# demo1.net
KiCad netlist of a schematic drawn in Altium Designer
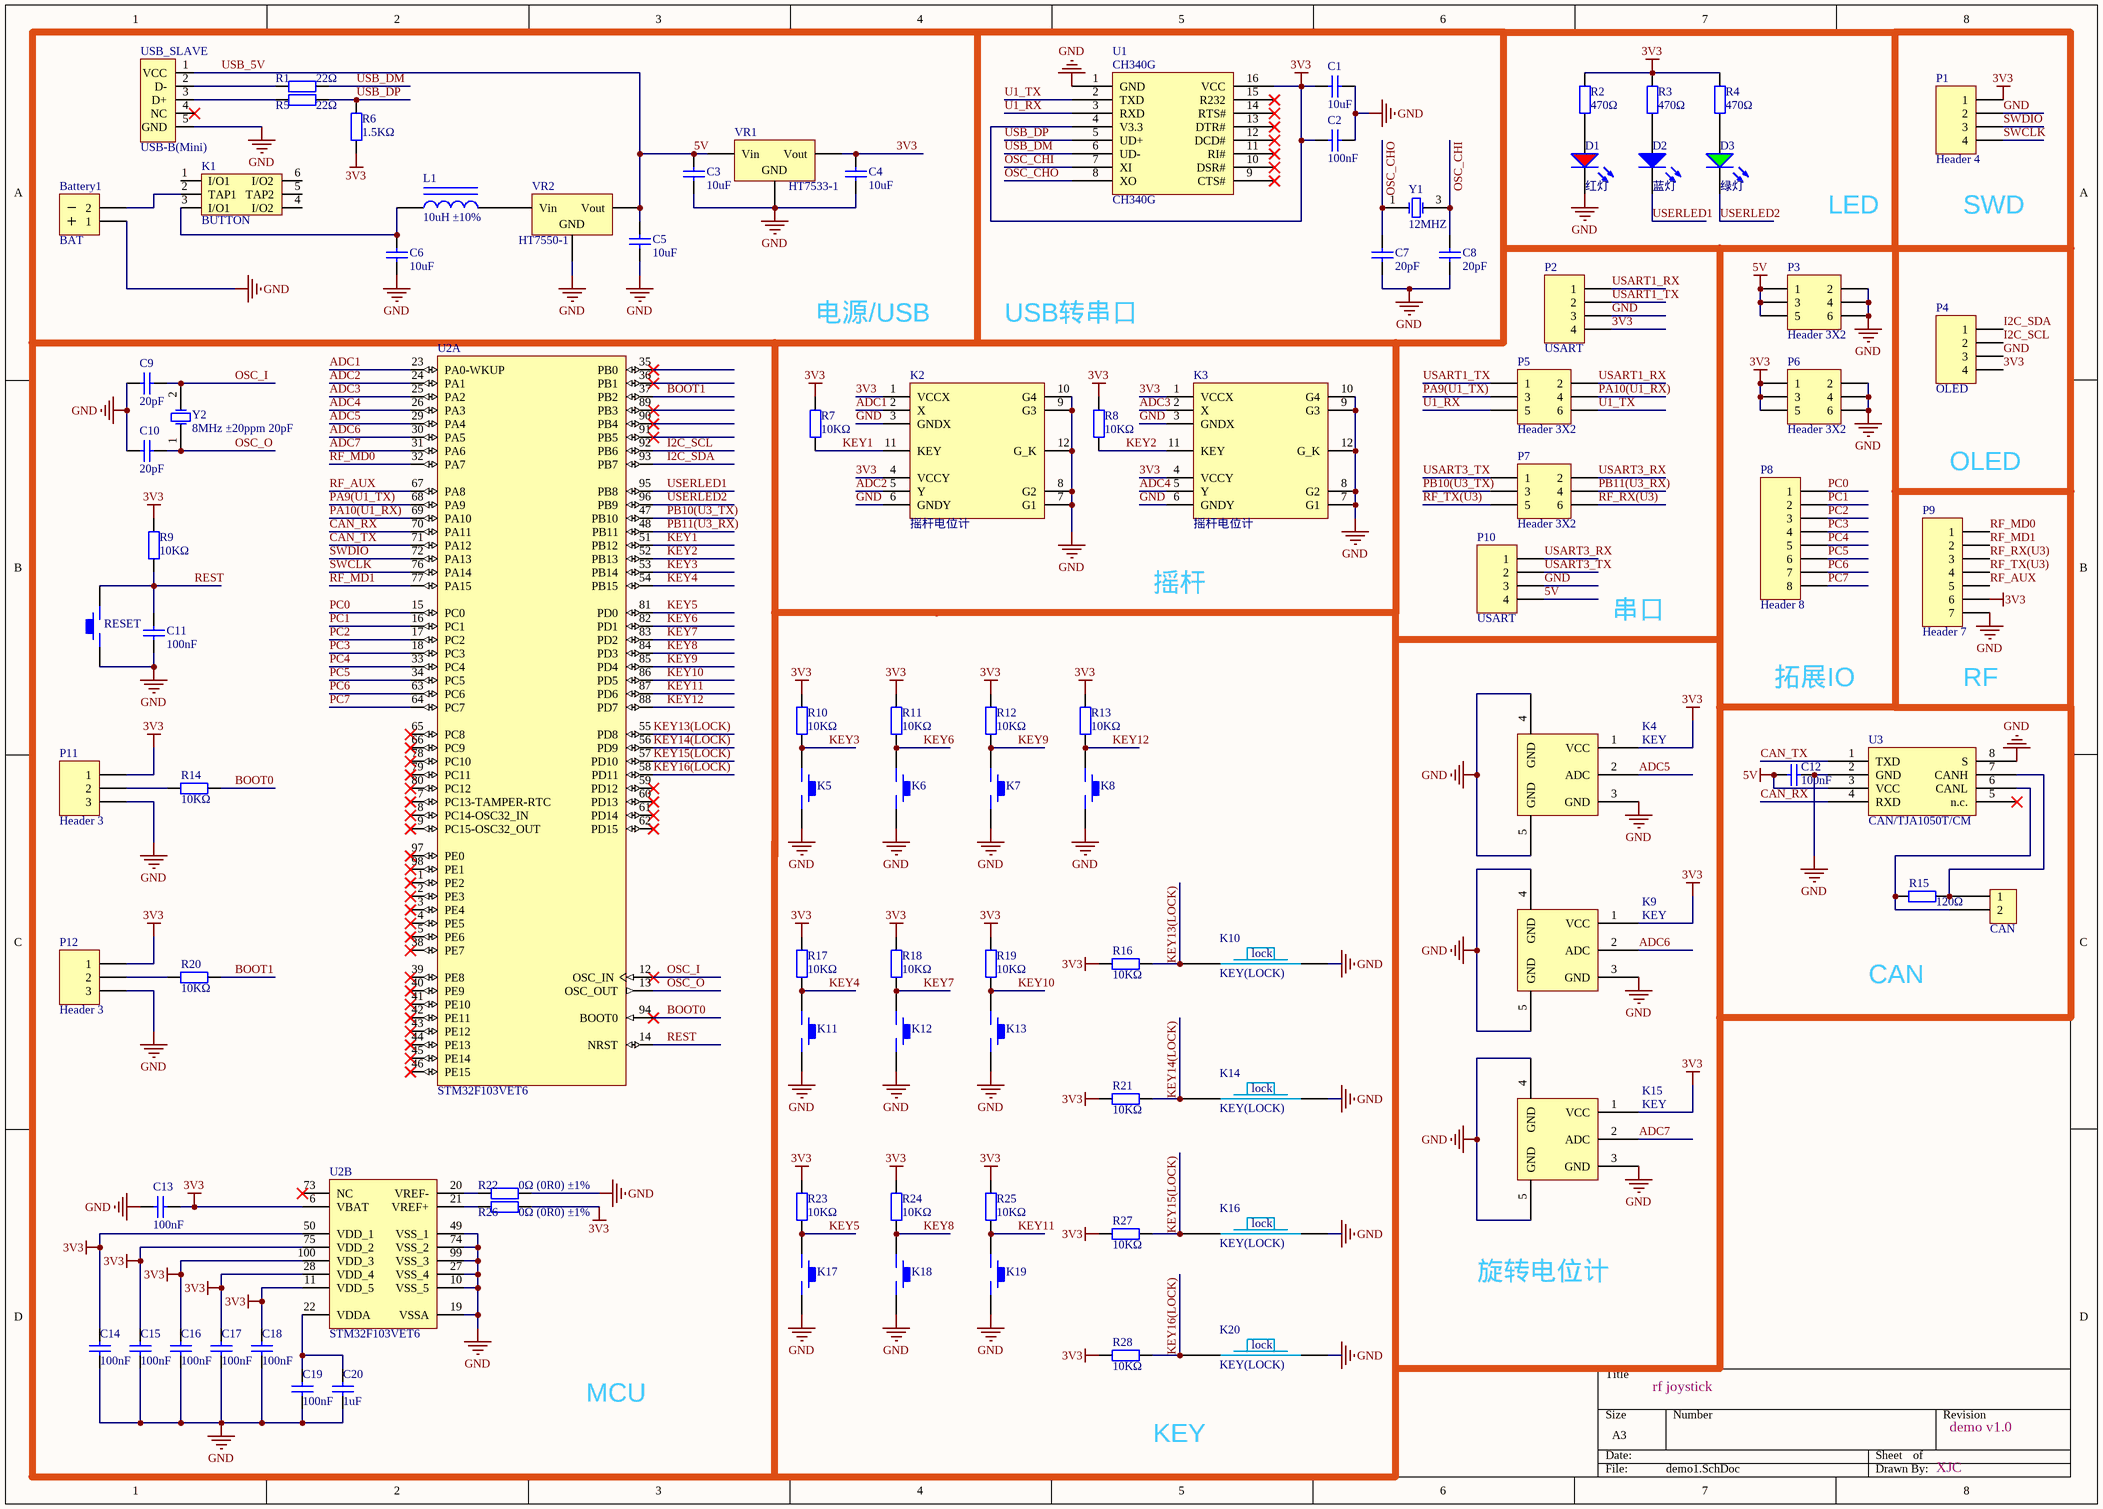
[diagram p0: demo1.SchDoc]

(export (version "E")
  (design (tool "Eeschema 10.0.6"))
  (components
    (comp (ref "*1") (value "CAN") (footprint "CAN") (libsource (lib "摇杆电位计") (part "CAN")))
    (comp (ref "Battery1")
      (value "BAT")
      (footprint "HDR1X2")
      (description "Header, 2-Pin")
      (fields (field (name "PUBLISHER") "mazhongwei"))
      (libsource (lib "RoboFly") (part "BAT"))
    )
    (comp (ref "C1")
      (value "10uF")
      (footprint "0603_C")
      (description "贴片电容")
      (libsource (lib "Cap") (part "0603 10uF (106) 10% 10V"))
    )
    (comp (ref "C2")
      (value "100nF")
      (footprint "0603_C")
      (description "贴片电容")
      (libsource (lib "Cap") (part "0603 100nF (104) 10% 50V"))
    )
    (comp (ref "C3")
      (value "10uF")
      (footprint "0603_C")
      (description "贴片电容")
      (libsource (lib "Cap") (part "0603 10uF (106) 10% 10V"))
    )
    (comp (ref "C4")
      (value "10uF")
      (footprint "0603_C")
      (description "贴片电容")
      (libsource (lib "Cap") (part "0603 10uF (106) 10% 10V"))
    )
    (comp (ref "C5")
      (value "10uF")
      (footprint "0603_C")
      (description "贴片电容")
      (libsource (lib "Cap") (part "0603 10uF (106) 10% 10V"))
    )
    (comp (ref "C6")
      (value "10uF")
      (footprint "0603_C")
      (description "贴片电容")
      (libsource (lib "Cap") (part "0603 10uF (106) 10% 10V"))
    )
    (comp (ref "C7")
      (value "20pF")
      (footprint "0603_C")
      (description "贴片电容")
      (libsource (lib "Cap") (part "0603 20pF (200) 5% 50V"))
    )
    (comp (ref "C8")
      (value "20pF")
      (footprint "0603_C")
      (description "贴片电容")
      (libsource (lib "Cap") (part "0603 20pF (200) 5% 50V"))
    )
    (comp (ref "C9")
      (value "20pF")
      (footprint "0603_C")
      (description "贴片电容")
      (libsource (lib "Cap") (part "0603 20pF (200) 5% 50V"))
    )
    (comp (ref "C10")
      (value "20pF")
      (footprint "0603_C")
      (description "贴片电容")
      (libsource (lib "Cap") (part "0603 20pF (200) 5% 50V"))
    )
    (comp (ref "C11")
      (value "100nF")
      (footprint "0603_C")
      (description "贴片电容")
      (libsource (lib "Cap") (part "0603 100nF (104) 10% 50V"))
    )
    (comp (ref "C12")
      (value "100nF")
      (footprint "0603_C")
      (description "贴片电容")
      (libsource (lib "Cap") (part "0603 100nF (104) 10% 50V"))
    )
    (comp (ref "C13")
      (value "100nF")
      (footprint "0603_C")
      (description "贴片电容")
      (libsource (lib "Cap") (part "0603 100nF (104) 10% 50V"))
    )
    (comp (ref "C14")
      (value "100nF")
      (footprint "0603_C")
      (description "贴片电容")
      (libsource (lib "Cap") (part "0603 100nF (104) 10% 50V"))
    )
    (comp (ref "C15")
      (value "100nF")
      (footprint "0603_C")
      (description "贴片电容")
      (libsource (lib "Cap") (part "0603 100nF (104) 10% 50V"))
    )
    (comp (ref "C16")
      (value "100nF")
      (footprint "0603_C")
      (description "贴片电容")
      (libsource (lib "Cap") (part "0603 100nF (104) 10% 50V"))
    )
    (comp (ref "C17")
      (value "100nF")
      (footprint "0603_C")
      (description "贴片电容")
      (libsource (lib "Cap") (part "0603 100nF (104) 10% 50V"))
    )
    (comp (ref "C18")
      (value "100nF")
      (footprint "0603_C")
      (description "贴片电容")
      (libsource (lib "Cap") (part "0603 100nF (104) 10% 50V"))
    )
    (comp (ref "C19")
      (value "100nF")
      (footprint "0603_C")
      (description "贴片电容")
      (libsource (lib "Cap") (part "0603 100nF (104) 10% 50V"))
    )
    (comp (ref "C20")
      (value "1uF")
      (footprint "0603_C")
      (description "贴片电容")
      (libsource (lib "Cap") (part "0603 1uF (105) 10% 50V"))
    )
    (comp (ref "D1")
      (value "红灯")
      (footprint "0603_LED_S1")
      (description "发光二极管")
      (libsource (lib "LED") (part "0603 红灯"))
    )
    (comp (ref "D2")
      (value "蓝灯")
      (footprint "0603_LED_S1")
      (description "发光二极管")
      (libsource (lib "LED") (part "0603 蓝灯"))
    )
    (comp (ref "D3")
      (value "绿灯")
      (footprint "0603_LED_S1")
      (description "发光二极管")
      (libsource (lib "LED") (part "0603 绿灯"))
    )
    (comp (ref "K1")
      (value "BUTTON")
      (footprint "BTN8.5*8.5")
      (libsource (lib "Explorer STM32F407封装库") (part "BUTTON"))
    )
    (comp (ref "K2") (value "摇杆电位计") (footprint "摇杆电位计") (libsource (lib "摇杆电位计") (part "摇杆电位计")))
    (comp (ref "K3") (value "摇杆电位计") (footprint "摇杆电位计") (libsource (lib "摇杆电位计") (part "摇杆电位计")))
    (comp (ref "K4") (value "KEY") (footprint "旋转电位计") (libsource (lib "摇杆电位计") (part "旋转电位计")))
    (comp (ref "K5")
      (value "KEY_M")
      (footprint "KEY_M")
      (libsource (lib "Explorer STM32F407封装库") (part "KEY_M"))
    )
    (comp (ref "K6")
      (value "KEY_M")
      (footprint "KEY_M")
      (libsource (lib "Explorer STM32F407封装库") (part "KEY_M"))
    )
    (comp (ref "K7")
      (value "KEY_M")
      (footprint "KEY_M")
      (libsource (lib "Explorer STM32F407封装库") (part "KEY_M"))
    )
    (comp (ref "K8")
      (value "KEY_M")
      (footprint "KEY_M")
      (libsource (lib "Explorer STM32F407封装库") (part "KEY_M"))
    )
    (comp (ref "K9") (value "KEY") (footprint "旋转电位计") (libsource (lib "摇杆电位计") (part "旋转电位计")))
    (comp (ref "K10") (value "KEY(LOCK)") (footprint "自锁按键") (libsource (lib "摇杆电位计") (part "自锁按键")))
    (comp (ref "K11")
      (value "KEY_M")
      (footprint "KEY_M")
      (libsource (lib "Explorer STM32F407封装库") (part "KEY_M"))
    )
    (comp (ref "K12")
      (value "KEY_M")
      (footprint "KEY_M")
      (libsource (lib "Explorer STM32F407封装库") (part "KEY_M"))
    )
    (comp (ref "K13")
      (value "KEY_M")
      (footprint "KEY_M")
      (libsource (lib "Explorer STM32F407封装库") (part "KEY_M"))
    )
    (comp (ref "K14") (value "KEY(LOCK)") (footprint "自锁按键") (libsource (lib "摇杆电位计") (part "自锁按键")))
    (comp (ref "K15") (value "KEY") (footprint "旋转电位计") (libsource (lib "摇杆电位计") (part "旋转电位计")))
    (comp (ref "K16") (value "KEY(LOCK)") (footprint "自锁按键") (libsource (lib "摇杆电位计") (part "自锁按键")))
    (comp (ref "K17")
      (value "KEY_M")
      (footprint "KEY_M")
      (libsource (lib "Explorer STM32F407封装库") (part "KEY_M"))
    )
    (comp (ref "K18")
      (value "KEY_M")
      (footprint "KEY_M")
      (libsource (lib "Explorer STM32F407封装库") (part "KEY_M"))
    )
    (comp (ref "K19")
      (value "KEY_M")
      (footprint "KEY_M")
      (libsource (lib "Explorer STM32F407封装库") (part "KEY_M"))
    )
    (comp (ref "K20") (value "KEY(LOCK)") (footprint "自锁按键") (libsource (lib "摇杆电位计") (part "自锁按键")))
    (comp (ref "L1")
      (value "10uH ±10%")
      (footprint "0603_L")
      (description "贴片电感")
      (libsource (lib "IUD") (part "0603 10uH 10%"))
    )
    (comp (ref "P1")
      (value "Header 4")
      (footprint "HDR1X4")
      (description "Header, 4-Pin")
      (fields (field (name "PUBLISHER") "Altium Limited"))
      (libsource (lib "Miscellaneous Connectors") (part "Header 4"))
    )
    (comp (ref "P2")
      (value "USART")
      (footprint "HDR1X4")
      (description "Header, 4-Pin")
      (fields (field (name "PUBLISHER") "Altium Limited"))
      (libsource (lib "Miscellaneous Connectors") (part "Header 4"))
    )
    (comp (ref "P3")
      (value "Header 3X2")
      (footprint "HDR2X3")
      (description "Header, 3-Pin, Dual row")
      (fields (field (name "PUBLISHER") "Altium Limited"))
      (libsource (lib "Miscellaneous Connectors") (part "Header 3X2"))
    )
    (comp (ref "P4")
      (value "OLED")
      (footprint "HDR1X4")
      (description "Header, 4-Pin")
      (fields (field (name "PUBLISHER") "Altium Limited"))
      (libsource (lib "Miscellaneous Connectors") (part "Header 4"))
    )
    (comp (ref "P5")
      (value "Header 3X2")
      (footprint "HDR2X3")
      (description "Header, 3-Pin, Dual row")
      (fields (field (name "PUBLISHER") "Altium Limited"))
      (libsource (lib "Miscellaneous Connectors") (part "Header 3X2"))
    )
    (comp (ref "P6")
      (value "Header 3X2")
      (footprint "HDR2X3")
      (description "Header, 3-Pin, Dual row")
      (fields (field (name "PUBLISHER") "Altium Limited"))
      (libsource (lib "Miscellaneous Connectors") (part "Header 3X2"))
    )
    (comp (ref "P7")
      (value "Header 3X2")
      (footprint "HDR2X3")
      (description "Header, 3-Pin, Dual row")
      (fields (field (name "PUBLISHER") "Altium Limited"))
      (libsource (lib "Miscellaneous Connectors") (part "Header 3X2"))
    )
    (comp (ref "P8")
      (value "Header 8")
      (footprint "HDR1X8")
      (description "Header, 8-Pin")
      (fields (field (name "PUBLISHER") "Altium Limited"))
      (libsource (lib "Miscellaneous Connectors") (part "Header 8"))
    )
    (comp (ref "P9")
      (value "Header 7")
      (footprint "HDR1X7")
      (description "Header, 7-Pin")
      (fields (field (name "PUBLISHER") "Altium Limited"))
      (libsource (lib "Miscellaneous Connectors") (part "Header 7"))
    )
    (comp (ref "P10")
      (value "USART")
      (footprint "HDR1X4")
      (description "Header, 4-Pin")
      (fields (field (name "PUBLISHER") "Altium Limited"))
      (libsource (lib "Miscellaneous Connectors") (part "Header 4"))
    )
    (comp (ref "P11")
      (value "Header 3")
      (footprint "HDR1X3")
      (description "Header, 3-Pin")
      (fields (field (name "PUBLISHER") "Altium Limited"))
      (libsource (lib "Miscellaneous Connectors") (part "Header 3"))
    )
    (comp (ref "P12")
      (value "Header 3")
      (footprint "HDR1X3")
      (description "Header, 3-Pin")
      (fields (field (name "PUBLISHER") "Altium Limited"))
      (libsource (lib "Miscellaneous Connectors") (part "Header 3"))
    )
    (comp (ref "R1")
      (value "22Ω")
      (footprint "0603_R")
      (description "贴片电阻")
      (libsource (lib "RES") (part "0603 22Ω (22R0) 1%"))
    )
    (comp (ref "R2")
      (value "470Ω")
      (footprint "0603_R")
      (description "贴片电阻")
      (libsource (lib "RES") (part "0603 470Ω (4700) 1%"))
    )
    (comp (ref "R3")
      (value "470Ω")
      (footprint "0603_R")
      (description "贴片电阻")
      (libsource (lib "RES") (part "0603 470Ω (4700) 1%"))
    )
    (comp (ref "R4")
      (value "470Ω")
      (footprint "0603_R")
      (description "贴片电阻")
      (libsource (lib "RES") (part "0603 470Ω (4700) 1%"))
    )
    (comp (ref "R5")
      (value "22Ω")
      (footprint "0603_R")
      (description "贴片电阻")
      (libsource (lib "RES") (part "0603 22Ω (22R0) 1%"))
    )
    (comp (ref "R6")
      (value "1.5KΩ")
      (footprint "0603_R")
      (description "贴片电阻")
      (libsource (lib "RES") (part "0603 1.5KΩ (1501) 1%"))
    )
    (comp (ref "R7")
      (value "10KΩ")
      (footprint "0603_R")
      (description "贴片电阻")
      (libsource (lib "RES") (part "0603 10KΩ (1002) 1%"))
    )
    (comp (ref "R8")
      (value "10KΩ")
      (footprint "0603_R")
      (description "贴片电阻")
      (libsource (lib "RES") (part "0603 10KΩ (1002) 1%"))
    )
    (comp (ref "R9")
      (value "10KΩ")
      (footprint "0603_R")
      (description "贴片电阻")
      (libsource (lib "RES") (part "0603 10KΩ (1002) 1%"))
    )
    (comp (ref "R10")
      (value "10KΩ")
      (footprint "0603_R")
      (description "贴片电阻")
      (libsource (lib "RES") (part "0603 10KΩ (1002) 1%"))
    )
    (comp (ref "R11")
      (value "10KΩ")
      (footprint "0603_R")
      (description "贴片电阻")
      (libsource (lib "RES") (part "0603 10KΩ (1002) 1%"))
    )
    (comp (ref "R12")
      (value "10KΩ")
      (footprint "0603_R")
      (description "贴片电阻")
      (libsource (lib "RES") (part "0603 10KΩ (1002) 1%"))
    )
    (comp (ref "R13")
      (value "10KΩ")
      (footprint "0603_R")
      (description "贴片电阻")
      (libsource (lib "RES") (part "0603 10KΩ (1002) 1%"))
    )
    (comp (ref "R14")
      (value "10KΩ")
      (footprint "0603_R")
      (description "贴片电阻")
      (libsource (lib "") (part "0603 10KΩ (1002) 1%_1"))
    )
    (comp (ref "R15")
      (value "120Ω")
      (footprint "0603_R")
      (description "贴片电阻")
      (libsource (lib "RES") (part "0603 120Ω (1200) 1%"))
    )
    (comp (ref "R16")
      (value "10KΩ")
      (footprint "0603_R")
      (description "贴片电阻")
      (libsource (lib "") (part "0603 10KΩ (1002) 1%_1"))
    )
    (comp (ref "R17")
      (value "10KΩ")
      (footprint "0603_R")
      (description "贴片电阻")
      (libsource (lib "RES") (part "0603 10KΩ (1002) 1%"))
    )
    (comp (ref "R18")
      (value "10KΩ")
      (footprint "0603_R")
      (description "贴片电阻")
      (libsource (lib "RES") (part "0603 10KΩ (1002) 1%"))
    )
    (comp (ref "R19")
      (value "10KΩ")
      (footprint "0603_R")
      (description "贴片电阻")
      (libsource (lib "RES") (part "0603 10KΩ (1002) 1%"))
    )
    (comp (ref "R20")
      (value "10KΩ")
      (footprint "0603_R")
      (description "贴片电阻")
      (libsource (lib "") (part "0603 10KΩ (1002) 1%_1"))
    )
    (comp (ref "R21")
      (value "10KΩ")
      (footprint "0603_R")
      (description "贴片电阻")
      (libsource (lib "") (part "0603 10KΩ (1002) 1%_1"))
    )
    (comp (ref "R22")
      (value "0Ω (0R0) ±1%")
      (footprint "0603_R")
      (description "贴片电阻")
      (libsource (lib "RES") (part "0603 0Ω (0R0) 1%"))
    )
    (comp (ref "R23")
      (value "10KΩ")
      (footprint "0603_R")
      (description "贴片电阻")
      (libsource (lib "RES") (part "0603 10KΩ (1002) 1%"))
    )
    (comp (ref "R24")
      (value "10KΩ")
      (footprint "0603_R")
      (description "贴片电阻")
      (libsource (lib "RES") (part "0603 10KΩ (1002) 1%"))
    )
    (comp (ref "R25")
      (value "10KΩ")
      (footprint "0603_R")
      (description "贴片电阻")
      (libsource (lib "RES") (part "0603 10KΩ (1002) 1%"))
    )
    (comp (ref "R26")
      (value "0Ω (0R0) ±1%")
      (footprint "0603_R")
      (description "贴片电阻")
      (libsource (lib "RES") (part "0603 0Ω (0R0) 1%"))
    )
    (comp (ref "R27")
      (value "10KΩ")
      (footprint "0603_R")
      (description "贴片电阻")
      (libsource (lib "") (part "0603 10KΩ (1002) 1%_1"))
    )
    (comp (ref "R28")
      (value "10KΩ")
      (footprint "0603_R")
      (description "贴片电阻")
      (libsource (lib "") (part "0603 10KΩ (1002) 1%_1"))
    )
    (comp (ref "RESET") (value "KEY_M") (footprint "KEY_M") (libsource (lib "") (part "KEY_M_1")))
    (comp (ref "U1")
      (value "CH340G")
      (footprint "SOIC-16_150mil")
      (description "USB")
      (libsource (lib "IC") (part "CH340G_[C14267]"))
    )
    (comp (ref "U2")
      (value "STM32F103VET6")
      (footprint "LQFP-100_14x14x05P")
      (description "ARM")
      (libsource (lib "MCU") (part "STM32F103VET6"))
    )
    (comp (ref "U3")
      (value "CAN/TJA1050T/CM")
      (footprint "SOIC-8_150mil")
      (description "CAN")
      (libsource (lib "IC") (part "CAN/TJA1050T/CM_[C6952]"))
    )
    (comp (ref "USB_SLAVE")
      (value "USB-B(Mini)")
      (footprint "USB/SM0.8-6H5")
      (libsource (lib "Explorer STM32F407封装库") (part "USB5"))
    )
    (comp (ref "VR1")
      (value "HT7533-1")
      (footprint "SOT-89(SOT-89-3)")
      (description "低压差线性稳压(LDO)")
      (libsource (lib "LDO") (part "SOT-89 HT7533-1"))
    )
    (comp (ref "VR2")
      (value "HT7550-1")
      (footprint "SOT-89(SOT-89-3)")
      (description "低压差线性稳压(LDO)")
      (libsource (lib "LDO") (part "SOT-89 HT7550-1"))
    )
    (comp (ref "Y1")
      (value "12MHZ")
      (footprint "SMD-3225_4P")
      (description "贴片晶振")
      (libsource (lib "CrystalOscillator") (part "SMD-3225_4P  12MHZ 20PF 10PPM"))
    )
    (comp (ref "Y2")
      (value "8MHz ±20ppm 20pF")
      (footprint "SMD-5032_2P")
      (description "贴片晶振")
      (libsource (lib "CrystalOscillator") (part "SMD-5032_2P 8MHz 20ppm 20pF"))
    )
  )
  (nets
    (net (code "1") (name "/ADC1") (class "Default")
      (node (ref "K2") (pin "2") (pinfunction "X_2") (pintype "passive"))
      (node (ref "U2") (pin "23") (pinfunction "PA0-WKUP_23") (pintype "bidirectional"))
    )
    (net (code "2") (name "/ADC2") (class "Default")
      (node (ref "K2") (pin "5") (pinfunction "Y_5") (pintype "passive"))
      (node (ref "U2") (pin "24") (pinfunction "PA1_24") (pintype "bidirectional"))
    )
    (net (code "3") (name "/ADC3") (class "Default")
      (node (ref "K3") (pin "2") (pinfunction "X_2") (pintype "passive"))
      (node (ref "U2") (pin "25") (pinfunction "PA2_25") (pintype "bidirectional"))
    )
    (net (code "4") (name "/ADC4") (class "Default")
      (node (ref "K3") (pin "5") (pinfunction "Y_5") (pintype "passive"))
      (node (ref "U2") (pin "26") (pinfunction "PA3_26") (pintype "bidirectional"))
    )
    (net (code "5") (name "/ADC5") (class "Default")
      (node (ref "K4") (pin "2") (pinfunction "ADC_2") (pintype "passive"))
      (node (ref "U2") (pin "29") (pinfunction "PA4_29") (pintype "bidirectional"))
    )
    (net (code "6") (name "/ADC6") (class "Default")
      (node (ref "K9") (pin "2") (pinfunction "ADC_2") (pintype "passive"))
      (node (ref "U2") (pin "30") (pinfunction "PA5_30") (pintype "bidirectional"))
    )
    (net (code "7") (name "/ADC7") (class "Default")
      (node (ref "K15") (pin "2") (pinfunction "ADC_2") (pintype "passive"))
      (node (ref "U2") (pin "31") (pinfunction "PA6_31") (pintype "bidirectional"))
    )
    (net (code "8") (name "/BOOT0") (class "Default")
      (node (ref "R14") (pin "1") (pinfunction "1_1") (pintype "passive"))
      (node (ref "U2") (pin "94") (pinfunction "BOOT0_94") (pintype "input"))
    )
    (net (code "9") (name "/BOOT1") (class "Default")
      (node (ref "R20") (pin "1") (pinfunction "1_1") (pintype "passive"))
      (node (ref "U2") (pin "37") (pinfunction "PB2_37") (pintype "bidirectional"))
    )
    (net (code "10") (name "/CAN_RX") (class "Default")
      (node (ref "U2") (pin "70") (pinfunction "PA11_70") (pintype "bidirectional"))
      (node (ref "U3") (pin "4") (pinfunction "RXD_4") (pintype "passive"))
    )
    (net (code "11") (name "/CAN_TX") (class "Default")
      (node (ref "U2") (pin "71") (pinfunction "PA12_71") (pintype "bidirectional"))
      (node (ref "U3") (pin "1") (pinfunction "TXD_1") (pintype "passive"))
    )
    (net (code "12") (name "/I2C_SCL") (class "Default")
      (node (ref "P4") (pin "2") (pinfunction "2_2") (pintype "passive"))
      (node (ref "U2") (pin "92") (pinfunction "PB6_92") (pintype "bidirectional"))
    )
    (net (code "13") (name "/I2C_SDA") (class "Default")
      (node (ref "P4") (pin "1") (pinfunction "1_1") (pintype "passive"))
      (node (ref "U2") (pin "93") (pinfunction "PB7_93") (pintype "bidirectional"))
    )
    (net (code "14") (name "/KEY1") (class "Default")
      (node (ref "K2") (pin "11") (pinfunction "KEY_11") (pintype "passive"))
      (node (ref "R7") (pin "1") (pinfunction "1_1") (pintype "passive"))
      (node (ref "U2") (pin "51") (pinfunction "PB12_51") (pintype "bidirectional"))
    )
    (net (code "15") (name "/KEY2") (class "Default")
      (node (ref "K3") (pin "11") (pinfunction "KEY_11") (pintype "passive"))
      (node (ref "R8") (pin "1") (pinfunction "1_1") (pintype "passive"))
      (node (ref "U2") (pin "52") (pinfunction "PB13_52") (pintype "bidirectional"))
    )
    (net (code "16") (name "/KEY3") (class "Default")
      (node (ref "K5") (pin "1") (pinfunction "1_1") (pintype "passive"))
      (node (ref "R10") (pin "1") (pinfunction "1_1") (pintype "passive"))
      (node (ref "U2") (pin "53") (pinfunction "PB14_53") (pintype "bidirectional"))
    )
    (net (code "17") (name "/KEY4") (class "Default")
      (node (ref "K11") (pin "1") (pinfunction "1_1") (pintype "passive"))
      (node (ref "R17") (pin "1") (pinfunction "1_1") (pintype "passive"))
      (node (ref "U2") (pin "54") (pinfunction "PB15_54") (pintype "bidirectional"))
    )
    (net (code "18") (name "/KEY5") (class "Default")
      (node (ref "K17") (pin "1") (pinfunction "1_1") (pintype "passive"))
      (node (ref "R23") (pin "1") (pinfunction "1_1") (pintype "passive"))
      (node (ref "U2") (pin "81") (pinfunction "PD0_81") (pintype "bidirectional"))
    )
    (net (code "19") (name "/KEY6") (class "Default")
      (node (ref "K6") (pin "1") (pinfunction "1_1") (pintype "passive"))
      (node (ref "R11") (pin "1") (pinfunction "1_1") (pintype "passive"))
      (node (ref "U2") (pin "82") (pinfunction "PD1_82") (pintype "bidirectional"))
    )
    (net (code "20") (name "/KEY7") (class "Default")
      (node (ref "K12") (pin "1") (pinfunction "1_1") (pintype "passive"))
      (node (ref "R18") (pin "1") (pinfunction "1_1") (pintype "passive"))
      (node (ref "U2") (pin "83") (pinfunction "PD2_83") (pintype "bidirectional"))
    )
    (net (code "21") (name "/KEY8") (class "Default")
      (node (ref "K18") (pin "1") (pinfunction "1_1") (pintype "passive"))
      (node (ref "R24") (pin "1") (pinfunction "1_1") (pintype "passive"))
      (node (ref "U2") (pin "84") (pinfunction "PD3_84") (pintype "bidirectional"))
    )
    (net (code "22") (name "/KEY9") (class "Default")
      (node (ref "K7") (pin "1") (pinfunction "1_1") (pintype "passive"))
      (node (ref "R12") (pin "1") (pinfunction "1_1") (pintype "passive"))
      (node (ref "U2") (pin "85") (pinfunction "PD4_85") (pintype "bidirectional"))
    )
    (net (code "23") (name "/KEY10") (class "Default")
      (node (ref "K13") (pin "1") (pinfunction "1_1") (pintype "passive"))
      (node (ref "R19") (pin "1") (pinfunction "1_1") (pintype "passive"))
      (node (ref "U2") (pin "86") (pinfunction "PD5_86") (pintype "bidirectional"))
    )
    (net (code "24") (name "/KEY11") (class "Default")
      (node (ref "K19") (pin "1") (pinfunction "1_1") (pintype "passive"))
      (node (ref "R25") (pin "1") (pinfunction "1_1") (pintype "passive"))
      (node (ref "U2") (pin "87") (pinfunction "PD6_87") (pintype "bidirectional"))
    )
    (net (code "25") (name "/KEY12") (class "Default")
      (node (ref "K8") (pin "1") (pinfunction "1_1") (pintype "passive"))
      (node (ref "R13") (pin "1") (pinfunction "1_1") (pintype "passive"))
      (node (ref "U2") (pin "88") (pinfunction "PD7_88") (pintype "bidirectional"))
    )
    (net (code "26") (name "/KEY13(LOCK)") (class "Default")
      (node (ref "K10") (pin "2") (pinfunction "2_2") (pintype "passive"))
      (node (ref "R16") (pin "1") (pinfunction "1_1") (pintype "passive"))
      (node (ref "U2") (pin "55") (pinfunction "PD8_55") (pintype "bidirectional"))
    )
    (net (code "27") (name "/KEY14(LOCK)") (class "Default")
      (node (ref "K14") (pin "2") (pinfunction "2_2") (pintype "passive"))
      (node (ref "R21") (pin "1") (pinfunction "1_1") (pintype "passive"))
      (node (ref "U2") (pin "56") (pinfunction "PD9_56") (pintype "bidirectional"))
    )
    (net (code "28") (name "/KEY15(LOCK)") (class "Default")
      (node (ref "K16") (pin "2") (pinfunction "2_2") (pintype "passive"))
      (node (ref "R27") (pin "1") (pinfunction "1_1") (pintype "passive"))
      (node (ref "U2") (pin "57") (pinfunction "PD10_57") (pintype "bidirectional"))
    )
    (net (code "29") (name "/KEY16(LOCK)") (class "Default")
      (node (ref "K20") (pin "2") (pinfunction "2_2") (pintype "passive"))
      (node (ref "R28") (pin "1") (pinfunction "1_1") (pintype "passive"))
      (node (ref "U2") (pin "58") (pinfunction "PD11_58") (pintype "bidirectional"))
    )
    (net (code "30") (name "/OSC_CHI") (class "Default")
      (node (ref "C8") (pin "2") (pinfunction "2_2") (pintype "passive"))
      (node (ref "U1") (pin "7") (pinfunction "XI_7") (pintype "passive"))
      (node (ref "Y1") (pin "3") (pinfunction "OSC2_3") (pintype "passive"))
    )
    (net (code "31") (name "/OSC_CHO") (class "Default")
      (node (ref "C7") (pin "2") (pinfunction "2_2") (pintype "passive"))
      (node (ref "U1") (pin "8") (pinfunction "XO_8") (pintype "passive"))
      (node (ref "Y1") (pin "1") (pinfunction "OSC1_1") (pintype "passive"))
    )
    (net (code "32") (name "/OSC_I") (class "Default")
      (node (ref "C9") (pin "2") (pinfunction "2_2") (pintype "passive"))
      (node (ref "U2") (pin "12") (pinfunction "OSC_IN_12") (pintype "input"))
      (node (ref "Y2") (pin "2") (pinfunction "OSC2_2") (pintype "passive"))
    )
    (net (code "33") (name "/OSC_O") (class "Default")
      (node (ref "C10") (pin "2") (pinfunction "2_2") (pintype "passive"))
      (node (ref "U2") (pin "13") (pinfunction "OSC_OUT_13") (pintype "output"))
      (node (ref "Y2") (pin "1") (pinfunction "OSC1_1") (pintype "passive"))
    )
    (net (code "34") (name "/PA9(U1_TX)") (class "Default")
      (node (ref "P5") (pin "3") (pinfunction "3_3") (pintype "passive"))
      (node (ref "U2") (pin "68") (pinfunction "PA9_68") (pintype "bidirectional"))
    )
    (net (code "35") (name "/PA10(U1_RX)") (class "Default")
      (node (ref "P5") (pin "4") (pinfunction "4_4") (pintype "passive"))
      (node (ref "U2") (pin "69") (pinfunction "PA10_69") (pintype "bidirectional"))
    )
    (net (code "36") (name "/PB10(U3_TX)") (class "Default")
      (node (ref "P7") (pin "3") (pinfunction "3_3") (pintype "passive"))
      (node (ref "U2") (pin "47") (pinfunction "PB10_47") (pintype "bidirectional"))
    )
    (net (code "37") (name "/PB11(U3_RX)") (class "Default")
      (node (ref "P7") (pin "4") (pinfunction "4_4") (pintype "passive"))
      (node (ref "U2") (pin "48") (pinfunction "PB11_48") (pintype "bidirectional"))
    )
    (net (code "38") (name "/PC0") (class "Default")
      (node (ref "P8") (pin "1") (pinfunction "1_1") (pintype "passive"))
      (node (ref "U2") (pin "15") (pinfunction "PC0_15") (pintype "bidirectional"))
    )
    (net (code "39") (name "/PC1") (class "Default")
      (node (ref "P8") (pin "2") (pinfunction "2_2") (pintype "passive"))
      (node (ref "U2") (pin "16") (pinfunction "PC1_16") (pintype "bidirectional"))
    )
    (net (code "40") (name "/PC2") (class "Default")
      (node (ref "P8") (pin "3") (pinfunction "3_3") (pintype "passive"))
      (node (ref "U2") (pin "17") (pinfunction "PC2_17") (pintype "bidirectional"))
    )
    (net (code "41") (name "/PC3") (class "Default")
      (node (ref "P8") (pin "4") (pinfunction "4_4") (pintype "passive"))
      (node (ref "U2") (pin "18") (pinfunction "PC3_18") (pintype "bidirectional"))
    )
    (net (code "42") (name "/PC4") (class "Default")
      (node (ref "P8") (pin "5") (pinfunction "5_5") (pintype "passive"))
      (node (ref "U2") (pin "33") (pinfunction "PC4_33") (pintype "bidirectional"))
    )
    (net (code "43") (name "/PC5") (class "Default")
      (node (ref "P8") (pin "6") (pinfunction "6_6") (pintype "passive"))
      (node (ref "U2") (pin "34") (pinfunction "PC5_34") (pintype "bidirectional"))
    )
    (net (code "44") (name "/PC6") (class "Default")
      (node (ref "P8") (pin "7") (pinfunction "7_7") (pintype "passive"))
      (node (ref "U2") (pin "63") (pinfunction "PC6_63") (pintype "bidirectional"))
    )
    (net (code "45") (name "/PC7") (class "Default")
      (node (ref "P8") (pin "8") (pinfunction "8_8") (pintype "passive"))
      (node (ref "U2") (pin "64") (pinfunction "PC7_64") (pintype "bidirectional"))
    )
    (net (code "46") (name "/REST") (class "Default")
      (node (ref "C11") (pin "2") (pinfunction "2_2") (pintype "passive"))
      (node (ref "R9") (pin "1") (pinfunction "1_1") (pintype "passive"))
      (node (ref "RESET") (pin "2") (pinfunction "2_2") (pintype "passive"))
      (node (ref "U2") (pin "14") (pinfunction "NRST_14") (pintype "bidirectional"))
    )
    (net (code "47") (name "/RF_AUX") (class "Default")
      (node (ref "P9") (pin "5") (pinfunction "5_5") (pintype "passive"))
      (node (ref "U2") (pin "67") (pinfunction "PA8_67") (pintype "bidirectional"))
    )
    (net (code "48") (name "/RF_MD0") (class "Default")
      (node (ref "P9") (pin "1") (pinfunction "1_1") (pintype "passive"))
      (node (ref "U2") (pin "32") (pinfunction "PA7_32") (pintype "bidirectional"))
    )
    (net (code "49") (name "/RF_MD1") (class "Default")
      (node (ref "P9") (pin "2") (pinfunction "2_2") (pintype "passive"))
      (node (ref "U2") (pin "77") (pinfunction "PA15_77") (pintype "bidirectional"))
    )
    (net (code "50") (name "/RF_RX(U3)") (class "Default")
      (node (ref "P7") (pin "6") (pinfunction "6_6") (pintype "passive"))
      (node (ref "P9") (pin "3") (pinfunction "3_3") (pintype "passive"))
    )
    (net (code "51") (name "/RF_TX(U3)") (class "Default")
      (node (ref "P7") (pin "5") (pinfunction "5_5") (pintype "passive"))
      (node (ref "P9") (pin "4") (pinfunction "4_4") (pintype "passive"))
    )
    (net (code "52") (name "/SWCLK") (class "Default")
      (node (ref "P1") (pin "4") (pinfunction "4_4") (pintype "passive"))
      (node (ref "U2") (pin "76") (pinfunction "PA14_76") (pintype "bidirectional"))
    )
    (net (code "53") (name "/SWDIO") (class "Default")
      (node (ref "P1") (pin "3") (pinfunction "3_3") (pintype "passive"))
      (node (ref "U2") (pin "72") (pinfunction "PA13_72") (pintype "bidirectional"))
    )
    (net (code "54") (name "/U1_RX") (class "Default")
      (node (ref "P5") (pin "5") (pinfunction "5_5") (pintype "passive"))
      (node (ref "U1") (pin "3") (pinfunction "RXD_3") (pintype "passive"))
    )
    (net (code "55") (name "/U1_TX") (class "Default")
      (node (ref "P5") (pin "6") (pinfunction "6_6") (pintype "passive"))
      (node (ref "U1") (pin "2") (pinfunction "TXD_2") (pintype "passive"))
    )
    (net (code "56") (name "/USART1_RX") (class "Default")
      (node (ref "P2") (pin "1") (pinfunction "1_1") (pintype "passive"))
      (node (ref "P5") (pin "2") (pinfunction "2_2") (pintype "passive"))
    )
    (net (code "57") (name "/USART1_TX") (class "Default")
      (node (ref "P2") (pin "2") (pinfunction "2_2") (pintype "passive"))
      (node (ref "P5") (pin "1") (pinfunction "1_1") (pintype "passive"))
    )
    (net (code "58") (name "/USART3_RX") (class "Default")
      (node (ref "P10") (pin "1") (pinfunction "1_1") (pintype "passive"))
      (node (ref "P7") (pin "2") (pinfunction "2_2") (pintype "passive"))
    )
    (net (code "59") (name "/USART3_TX") (class "Default")
      (node (ref "P10") (pin "2") (pinfunction "2_2") (pintype "passive"))
      (node (ref "P7") (pin "1") (pinfunction "1_1") (pintype "passive"))
    )
    (net (code "60") (name "/USB_DM") (class "Default")
      (node (ref "R1") (pin "2") (pinfunction "2_2") (pintype "passive"))
      (node (ref "U1") (pin "6") (pinfunction "UD-_6") (pintype "passive"))
    )
    (net (code "61") (name "/USB_DP") (class "Default")
      (node (ref "R5") (pin "2") (pinfunction "2_2") (pintype "passive"))
      (node (ref "R6") (pin "2") (pinfunction "2_2") (pintype "passive"))
      (node (ref "U1") (pin "5") (pinfunction "UD+_5") (pintype "passive"))
    )
    (net (code "62") (name "/USERLED1") (class "Default")
      (node (ref "D2") (pin "K") (pinfunction "K_K") (pintype "passive"))
      (node (ref "U2") (pin "95") (pinfunction "PB8_95") (pintype "bidirectional"))
    )
    (net (code "63") (name "/USERLED2") (class "Default")
      (node (ref "D3") (pin "K") (pinfunction "K_K") (pintype "passive"))
      (node (ref "U2") (pin "96") (pinfunction "PB9_96") (pintype "bidirectional"))
    )
    (net (code "64") (name "3V3") (class "Default")
      (node (ref "C1") (pin "1") (pinfunction "1_1") (pintype "passive"))
      (node (ref "C13") (pin "1") (pinfunction "1_1") (pintype "passive"))
      (node (ref "C14") (pin "1") (pinfunction "1_1") (pintype "passive"))
      (node (ref "C15") (pin "1") (pinfunction "1_1") (pintype "passive"))
      (node (ref "C16") (pin "1") (pinfunction "1_1") (pintype "passive"))
      (node (ref "C17") (pin "1") (pinfunction "1_1") (pintype "passive"))
      (node (ref "C18") (pin "1") (pinfunction "1_1") (pintype "passive"))
      (node (ref "C2") (pin "1") (pinfunction "1_1") (pintype "passive"))
      (node (ref "C4") (pin "2") (pinfunction "2_2") (pintype "passive"))
      (node (ref "K15") (pin "1") (pinfunction "VCC_1") (pintype "passive"))
      (node (ref "K2") (pin "1") (pinfunction "VCCX_1") (pintype "passive"))
      (node (ref "K2") (pin "4") (pinfunction "VCCY_4") (pintype "passive"))
      (node (ref "K3") (pin "1") (pinfunction "VCCX_1") (pintype "passive"))
      (node (ref "K3") (pin "4") (pinfunction "VCCY_4") (pintype "passive"))
      (node (ref "K4") (pin "1") (pinfunction "VCC_1") (pintype "passive"))
      (node (ref "K9") (pin "1") (pinfunction "VCC_1") (pintype "passive"))
      (node (ref "P1") (pin "1") (pinfunction "1_1") (pintype "passive"))
      (node (ref "P11") (pin "1") (pinfunction "1_1") (pintype "passive"))
      (node (ref "P12") (pin "1") (pinfunction "1_1") (pintype "passive"))
      (node (ref "P2") (pin "4") (pinfunction "4_4") (pintype "passive"))
      (node (ref "P4") (pin "4") (pinfunction "4_4") (pintype "passive"))
      (node (ref "P6") (pin "1") (pinfunction "1_1") (pintype "passive"))
      (node (ref "P6") (pin "3") (pinfunction "3_3") (pintype "passive"))
      (node (ref "P6") (pin "5") (pinfunction "5_5") (pintype "passive"))
      (node (ref "P9") (pin "6") (pinfunction "6_6") (pintype "passive"))
      (node (ref "R10") (pin "2") (pinfunction "2_2") (pintype "passive"))
      (node (ref "R11") (pin "2") (pinfunction "2_2") (pintype "passive"))
      (node (ref "R12") (pin "2") (pinfunction "2_2") (pintype "passive"))
      (node (ref "R13") (pin "2") (pinfunction "2_2") (pintype "passive"))
      (node (ref "R16") (pin "2") (pinfunction "2_2") (pintype "passive"))
      (node (ref "R17") (pin "2") (pinfunction "2_2") (pintype "passive"))
      (node (ref "R18") (pin "2") (pinfunction "2_2") (pintype "passive"))
      (node (ref "R19") (pin "2") (pinfunction "2_2") (pintype "passive"))
      (node (ref "R2") (pin "2") (pinfunction "2_2") (pintype "passive"))
      (node (ref "R21") (pin "2") (pinfunction "2_2") (pintype "passive"))
      (node (ref "R23") (pin "2") (pinfunction "2_2") (pintype "passive"))
      (node (ref "R24") (pin "2") (pinfunction "2_2") (pintype "passive"))
      (node (ref "R25") (pin "2") (pinfunction "2_2") (pintype "passive"))
      (node (ref "R26") (pin "2") (pinfunction "2_2") (pintype "passive"))
      (node (ref "R27") (pin "2") (pinfunction "2_2") (pintype "passive"))
      (node (ref "R28") (pin "2") (pinfunction "2_2") (pintype "passive"))
      (node (ref "R3") (pin "2") (pinfunction "2_2") (pintype "passive"))
      (node (ref "R4") (pin "2") (pinfunction "2_2") (pintype "passive"))
      (node (ref "R6") (pin "1") (pinfunction "1_1") (pintype "passive"))
      (node (ref "R7") (pin "2") (pinfunction "2_2") (pintype "passive"))
      (node (ref "R8") (pin "2") (pinfunction "2_2") (pintype "passive"))
      (node (ref "R9") (pin "2") (pinfunction "2_2") (pintype "passive"))
      (node (ref "U1") (pin "16") (pinfunction "VCC_16") (pintype "passive"))
      (node (ref "U1") (pin "4") (pinfunction "V3.3_4") (pintype "passive"))
      (node (ref "U2") (pin "100") (pinfunction "VDD_3_100") (pintype "power_in"))
      (node (ref "U2") (pin "11") (pinfunction "VDD_5_11") (pintype "power_in"))
      (node (ref "U2") (pin "28") (pinfunction "VDD_4_28") (pintype "power_in"))
      (node (ref "U2") (pin "50") (pinfunction "VDD_1_50") (pintype "power_in"))
      (node (ref "U2") (pin "6") (pinfunction "VBAT_6") (pintype "power_in"))
      (node (ref "U2") (pin "75") (pinfunction "VDD_2_75") (pintype "power_in"))
      (node (ref "VR1") (pin "3") (pinfunction "Vout_3") (pintype "passive"))
    )
    (net (code "65") (name "5V") (class "Default")
      (node (ref "C12") (pin "1") (pinfunction "1_1") (pintype "passive"))
      (node (ref "C3") (pin "2") (pinfunction "2_2") (pintype "passive"))
      (node (ref "C5") (pin "2") (pinfunction "2_2") (pintype "passive"))
      (node (ref "P10") (pin "4") (pinfunction "4_4") (pintype "passive"))
      (node (ref "P3") (pin "1") (pinfunction "1_1") (pintype "passive"))
      (node (ref "P3") (pin "3") (pinfunction "3_3") (pintype "passive"))
      (node (ref "P3") (pin "5") (pinfunction "5_5") (pintype "passive"))
      (node (ref "U3") (pin "3") (pinfunction "VCC_3") (pintype "passive"))
      (node (ref "USB_SLAVE") (pin "1") (pinfunction "VCC_1") (pintype "passive"))
      (node (ref "VR1") (pin "2") (pinfunction "Vin_2") (pintype "passive"))
      (node (ref "VR2") (pin "3") (pinfunction "Vout_3") (pintype "passive"))
    )
    (net (code "66") (name "GND") (class "Default")
      (node (ref "Battery1") (pin "1") (pinfunction "1_1") (pintype "passive"))
      (node (ref "C1") (pin "2") (pinfunction "2_2") (pintype "passive"))
      (node (ref "C10") (pin "1") (pinfunction "1_1") (pintype "passive"))
      (node (ref "C11") (pin "1") (pinfunction "1_1") (pintype "passive"))
      (node (ref "C12") (pin "2") (pinfunction "2_2") (pintype "passive"))
      (node (ref "C13") (pin "2") (pinfunction "2_2") (pintype "passive"))
      (node (ref "C14") (pin "2") (pinfunction "2_2") (pintype "passive"))
      (node (ref "C15") (pin "2") (pinfunction "2_2") (pintype "passive"))
      (node (ref "C16") (pin "2") (pinfunction "2_2") (pintype "passive"))
      (node (ref "C17") (pin "2") (pinfunction "2_2") (pintype "passive"))
      (node (ref "C18") (pin "2") (pinfunction "2_2") (pintype "passive"))
      (node (ref "C19") (pin "2") (pinfunction "2_2") (pintype "passive"))
      (node (ref "C2") (pin "2") (pinfunction "2_2") (pintype "passive"))
      (node (ref "C20") (pin "1") (pinfunction "1_1") (pintype "passive"))
      (node (ref "C3") (pin "1") (pinfunction "1_1") (pintype "passive"))
      (node (ref "C4") (pin "1") (pinfunction "1_1") (pintype "passive"))
      (node (ref "C5") (pin "1") (pinfunction "1_1") (pintype "passive"))
      (node (ref "C6") (pin "1") (pinfunction "1_1") (pintype "passive"))
      (node (ref "C7") (pin "1") (pinfunction "1_1") (pintype "passive"))
      (node (ref "C8") (pin "1") (pinfunction "1_1") (pintype "passive"))
      (node (ref "C9") (pin "1") (pinfunction "1_1") (pintype "passive"))
      (node (ref "D1") (pin "K") (pinfunction "K_K") (pintype "passive"))
      (node (ref "K10") (pin "1") (pinfunction "1_1") (pintype "passive"))
      (node (ref "K11") (pin "2") (pinfunction "2_2") (pintype "passive"))
      (node (ref "K12") (pin "2") (pinfunction "2_2") (pintype "passive"))
      (node (ref "K13") (pin "2") (pinfunction "2_2") (pintype "passive"))
      (node (ref "K14") (pin "1") (pinfunction "1_1") (pintype "passive"))
      (node (ref "K15") (pin "3") (pinfunction "GND_3") (pintype "passive"))
      (node (ref "K15") (pin "4") (pinfunction "GND_4") (pintype "passive"))
      (node (ref "K15") (pin "5") (pinfunction "GND_5") (pintype "passive"))
      (node (ref "K16") (pin "1") (pinfunction "1_1") (pintype "passive"))
      (node (ref "K17") (pin "2") (pinfunction "2_2") (pintype "passive"))
      (node (ref "K18") (pin "2") (pinfunction "2_2") (pintype "passive"))
      (node (ref "K19") (pin "2") (pinfunction "2_2") (pintype "passive"))
      (node (ref "K2") (pin "10") (pinfunction "G4_10") (pintype "passive"))
      (node (ref "K2") (pin "12") (pinfunction "G_K_12") (pintype "passive"))
      (node (ref "K2") (pin "3") (pinfunction "GNDX_3") (pintype "passive"))
      (node (ref "K2") (pin "6") (pinfunction "GNDY_6") (pintype "passive"))
      (node (ref "K2") (pin "7") (pinfunction "G1_7") (pintype "passive"))
      (node (ref "K2") (pin "8") (pinfunction "G2_8") (pintype "passive"))
      (node (ref "K2") (pin "9") (pinfunction "G3_9") (pintype "passive"))
      (node (ref "K20") (pin "1") (pinfunction "1_1") (pintype "passive"))
      (node (ref "K3") (pin "10") (pinfunction "G4_10") (pintype "passive"))
      (node (ref "K3") (pin "12") (pinfunction "G_K_12") (pintype "passive"))
      (node (ref "K3") (pin "3") (pinfunction "GNDX_3") (pintype "passive"))
      (node (ref "K3") (pin "6") (pinfunction "GNDY_6") (pintype "passive"))
      (node (ref "K3") (pin "7") (pinfunction "G1_7") (pintype "passive"))
      (node (ref "K3") (pin "8") (pinfunction "G2_8") (pintype "passive"))
      (node (ref "K3") (pin "9") (pinfunction "G3_9") (pintype "passive"))
      (node (ref "K4") (pin "3") (pinfunction "GND_3") (pintype "passive"))
      (node (ref "K4") (pin "4") (pinfunction "GND_4") (pintype "passive"))
      (node (ref "K4") (pin "5") (pinfunction "GND_5") (pintype "passive"))
      (node (ref "K5") (pin "2") (pinfunction "2_2") (pintype "passive"))
      (node (ref "K6") (pin "2") (pinfunction "2_2") (pintype "passive"))
      (node (ref "K7") (pin "2") (pinfunction "2_2") (pintype "passive"))
      (node (ref "K8") (pin "2") (pinfunction "2_2") (pintype "passive"))
      (node (ref "K9") (pin "3") (pinfunction "GND_3") (pintype "passive"))
      (node (ref "K9") (pin "4") (pinfunction "GND_4") (pintype "passive"))
      (node (ref "K9") (pin "5") (pinfunction "GND_5") (pintype "passive"))
      (node (ref "P1") (pin "2") (pinfunction "2_2") (pintype "passive"))
      (node (ref "P10") (pin "3") (pinfunction "3_3") (pintype "passive"))
      (node (ref "P11") (pin "3") (pinfunction "3_3") (pintype "passive"))
      (node (ref "P12") (pin "3") (pinfunction "3_3") (pintype "passive"))
      (node (ref "P2") (pin "3") (pinfunction "3_3") (pintype "passive"))
      (node (ref "P3") (pin "2") (pinfunction "2_2") (pintype "passive"))
      (node (ref "P3") (pin "4") (pinfunction "4_4") (pintype "passive"))
      (node (ref "P3") (pin "6") (pinfunction "6_6") (pintype "passive"))
      (node (ref "P4") (pin "3") (pinfunction "3_3") (pintype "passive"))
      (node (ref "P6") (pin "2") (pinfunction "2_2") (pintype "passive"))
      (node (ref "P6") (pin "4") (pinfunction "4_4") (pintype "passive"))
      (node (ref "P6") (pin "6") (pinfunction "6_6") (pintype "passive"))
      (node (ref "P9") (pin "7") (pinfunction "7_7") (pintype "passive"))
      (node (ref "R22") (pin "2") (pinfunction "2_2") (pintype "passive"))
      (node (ref "RESET") (pin "1") (pinfunction "1_1") (pintype "passive"))
      (node (ref "U1") (pin "1") (pinfunction "GND_1") (pintype "passive"))
      (node (ref "U2") (pin "10") (pinfunction "VSS_5_10") (pintype "power_in"))
      (node (ref "U2") (pin "19") (pinfunction "VSSA_19") (pintype "power_in"))
      (node (ref "U2") (pin "27") (pinfunction "VSS_4_27") (pintype "power_in"))
      (node (ref "U2") (pin "49") (pinfunction "VSS_1_49") (pintype "power_in"))
      (node (ref "U2") (pin "74") (pinfunction "VSS_2_74") (pintype "power_in"))
      (node (ref "U2") (pin "99") (pinfunction "VSS_3_99") (pintype "power_in"))
      (node (ref "U3") (pin "2") (pinfunction "GND_2") (pintype "passive"))
      (node (ref "U3") (pin "8") (pinfunction "S_8") (pintype "passive"))
      (node (ref "USB_SLAVE") (pin "5") (pinfunction "GND_5") (pintype "passive"))
      (node (ref "VR1") (pin "1") (pinfunction "GND_1") (pintype "passive"))
      (node (ref "VR2") (pin "1") (pinfunction "GND_1") (pintype "passive"))
    )
    (net (code "67") (name "Net-(C6-Pad2)") (class "Default")
      (node (ref "C6") (pin "2") (pinfunction "2_2") (pintype "passive"))
      (node (ref "K1") (pin "3") (pinfunction "I/O1_3") (pintype "passive"))
      (node (ref "L1") (pin "1") (pinfunction "1_1") (pintype "passive"))
    )
    (net (code "68") (name "Net-(D1-PadA)") (class "Default")
      (node (ref "D1") (pin "A") (pinfunction "A_A") (pintype "passive"))
      (node (ref "R2") (pin "1") (pinfunction "1_1") (pintype "passive"))
    )
    (net (code "69") (name "Net-(D2-PadA)") (class "Default")
      (node (ref "D2") (pin "A") (pinfunction "A_A") (pintype "passive"))
      (node (ref "R3") (pin "1") (pinfunction "1_1") (pintype "passive"))
    )
    (net (code "70") (name "Net-(D3-PadA)") (class "Default")
      (node (ref "D3") (pin "A") (pinfunction "A_A") (pintype "passive"))
      (node (ref "R4") (pin "1") (pinfunction "1_1") (pintype "passive"))
    )
    (net (code "71") (name "Net-(K1-TAP1)") (class "Default")
      (node (ref "Battery1") (pin "2") (pinfunction "2_2") (pintype "passive"))
      (node (ref "K1") (pin "2") (pinfunction "TAP1_2") (pintype "passive"))
    )
    (net (code "72") (name "Net-(P11-Pad2)") (class "Default")
      (node (ref "P11") (pin "2") (pinfunction "2_2") (pintype "passive"))
      (node (ref "R14") (pin "2") (pinfunction "2_2") (pintype "passive"))
    )
    (net (code "73") (name "Net-(P12-Pad2)") (class "Default")
      (node (ref "P12") (pin "2") (pinfunction "2_2") (pintype "passive"))
      (node (ref "R20") (pin "2") (pinfunction "2_2") (pintype "passive"))
    )
    (net (code "74") (name "Net-(U2B-VDDA)") (class "Default")
      (node (ref "C19") (pin "1") (pinfunction "1_1") (pintype "passive"))
      (node (ref "C20") (pin "2") (pinfunction "2_2") (pintype "passive"))
      (node (ref "U2") (pin "22") (pinfunction "VDDA_22") (pintype "power_in"))
    )
    (net (code "75") (name "Net-(U2B-VREF+)") (class "Default")
      (node (ref "R26") (pin "1") (pinfunction "1_1") (pintype "passive"))
      (node (ref "U2") (pin "21") (pinfunction "VREF+_21") (pintype "power_in"))
    )
    (net (code "76") (name "Net-(U2B-VREF-)") (class "Default")
      (node (ref "R22") (pin "1") (pinfunction "1_1") (pintype "passive"))
      (node (ref "U2") (pin "20") (pinfunction "VREF-_20") (pintype "power_in"))
    )
    (net (code "77") (name "Net-(U3-CANH)") (class "Default")
      (node (ref "*1") (pin "1") (pinfunction "1_1") (pintype "passive"))
      (node (ref "R15") (pin "2") (pinfunction "2_2") (pintype "passive"))
      (node (ref "U3") (pin "7") (pinfunction "CANH_7") (pintype "passive"))
    )
    (net (code "78") (name "Net-(U3-CANL)") (class "Default")
      (node (ref "*1") (pin "2") (pinfunction "2_2") (pintype "passive"))
      (node (ref "R15") (pin "1") (pinfunction "1_1") (pintype "passive"))
      (node (ref "U3") (pin "6") (pinfunction "CANL_6") (pintype "passive"))
    )
    (net (code "79") (name "Net-(USB_SLAVE-D+)") (class "Default")
      (node (ref "R5") (pin "1") (pinfunction "1_1") (pintype "passive"))
      (node (ref "USB_SLAVE") (pin "3") (pinfunction "D+_3") (pintype "passive"))
    )
    (net (code "80") (name "Net-(USB_SLAVE-D-)") (class "Default")
      (node (ref "R1") (pin "1") (pinfunction "1_1") (pintype "passive"))
      (node (ref "USB_SLAVE") (pin "2") (pinfunction "D-_2") (pintype "passive"))
    )
    (net (code "81") (name "Net-(VR2-Vin)") (class "Default")
      (node (ref "L1") (pin "2") (pinfunction "2_2") (pintype "passive"))
      (node (ref "VR2") (pin "2") (pinfunction "Vin_2") (pintype "passive"))
    )
    (net (code "82") (name "unconnected-(K1-I{slash}O1-Pad1)") (class "Default")
      (node (ref "K1") (pin "1") (pinfunction "I/O1_1") (pintype "passive"))
    )
    (net (code "83") (name "unconnected-(K1-I{slash}O2-Pad4)") (class "Default")
      (node (ref "K1") (pin "4") (pinfunction "I/O2_4") (pintype "passive"))
    )
    (net (code "84") (name "unconnected-(K1-I{slash}O2-Pad6)") (class "Default")
      (node (ref "K1") (pin "6") (pinfunction "I/O2_6") (pintype "passive"))
    )
    (net (code "85") (name "unconnected-(K1-TAP2-Pad5)") (class "Default")
      (node (ref "K1") (pin "5") (pinfunction "TAP2_5") (pintype "passive"))
    )
    (net (code "86") (name "unconnected-(U1-CTS#-Pad9)") (class "Default")
      (node (ref "U1") (pin "9") (pinfunction "CTS#_9") (pintype "passive+no_connect"))
    )
    (net (code "87") (name "unconnected-(U1-DCD#-Pad12)") (class "Default")
      (node (ref "U1") (pin "12") (pinfunction "DCD#_12") (pintype "passive+no_connect"))
    )
    (net (code "88") (name "unconnected-(U1-DSR#-Pad10)") (class "Default")
      (node (ref "U1") (pin "10") (pinfunction "DSR#_10") (pintype "passive+no_connect"))
    )
    (net (code "89") (name "unconnected-(U1-DTR#-Pad13)") (class "Default")
      (node (ref "U1") (pin "13") (pinfunction "DTR#_13") (pintype "passive+no_connect"))
    )
    (net (code "90") (name "unconnected-(U1-R232-Pad15)") (class "Default")
      (node (ref "U1") (pin "15") (pinfunction "R232_15") (pintype "passive+no_connect"))
    )
    (net (code "91") (name "unconnected-(U1-RI#-Pad11)") (class "Default")
      (node (ref "U1") (pin "11") (pinfunction "RI#_11") (pintype "passive+no_connect"))
    )
    (net (code "92") (name "unconnected-(U1-RTS#-Pad14)") (class "Default")
      (node (ref "U1") (pin "14") (pinfunction "RTS#_14") (pintype "passive+no_connect"))
    )
    (net (code "93") (name "unconnected-(U2A-PB0-Pad35)") (class "Default")
      (node (ref "U2") (pin "35") (pinfunction "PB0_35") (pintype "bidirectional+no_connect"))
    )
    (net (code "94") (name "unconnected-(U2A-PB1-Pad36)") (class "Default")
      (node (ref "U2") (pin "36") (pinfunction "PB1_36") (pintype "bidirectional+no_connect"))
    )
    (net (code "95") (name "unconnected-(U2A-PB3-Pad89)") (class "Default")
      (node (ref "U2") (pin "89") (pinfunction "PB3_89") (pintype "bidirectional+no_connect"))
    )
    (net (code "96") (name "unconnected-(U2A-PB4-Pad90)") (class "Default")
      (node (ref "U2") (pin "90") (pinfunction "PB4_90") (pintype "bidirectional+no_connect"))
    )
    (net (code "97") (name "unconnected-(U2A-PB5-Pad91)") (class "Default")
      (node (ref "U2") (pin "91") (pinfunction "PB5_91") (pintype "bidirectional+no_connect"))
    )
    (net (code "98") (name "unconnected-(U2A-PC8-Pad65)") (class "Default")
      (node (ref "U2") (pin "65") (pinfunction "PC8_65") (pintype "bidirectional+no_connect"))
    )
    (net (code "99") (name "unconnected-(U2A-PC9-Pad66)") (class "Default")
      (node (ref "U2") (pin "66") (pinfunction "PC9_66") (pintype "bidirectional+no_connect"))
    )
    (net (code "100") (name "unconnected-(U2A-PC10-Pad78)") (class "Default")
      (node (ref "U2") (pin "78") (pinfunction "PC10_78") (pintype "bidirectional+no_connect"))
    )
    (net (code "101") (name "unconnected-(U2A-PC11-Pad79)") (class "Default")
      (node (ref "U2") (pin "79") (pinfunction "PC11_79") (pintype "bidirectional+no_connect"))
    )
    (net (code "102") (name "unconnected-(U2A-PC12-Pad80)") (class "Default")
      (node (ref "U2") (pin "80") (pinfunction "PC12_80") (pintype "bidirectional+no_connect"))
    )
    (net (code "103") (name "unconnected-(U2A-PC13-TAMPER-RTC-Pad7)") (class "Default")
      (node (ref "U2") (pin "7") (pinfunction "PC13-TAMPER-RTC_7") (pintype "bidirectional+no_connect"))
    )
    (net (code "104") (name "unconnected-(U2A-PC14-OSC32_IN-Pad8)") (class "Default")
      (node (ref "U2") (pin "8") (pinfunction "PC14-OSC32_IN_8") (pintype "bidirectional+no_connect"))
    )
    (net (code "105") (name "unconnected-(U2A-PC15-OSC32_OUT-Pad9)") (class "Default")
      (node (ref "U2") (pin "9") (pinfunction "PC15-OSC32_OUT_9") (pintype "bidirectional+no_connect"))
    )
    (net (code "106") (name "unconnected-(U2A-PD12-Pad59)") (class "Default")
      (node (ref "U2") (pin "59") (pinfunction "PD12_59") (pintype "bidirectional+no_connect"))
    )
    (net (code "107") (name "unconnected-(U2A-PD13-Pad60)") (class "Default")
      (node (ref "U2") (pin "60") (pinfunction "PD13_60") (pintype "bidirectional+no_connect"))
    )
    (net (code "108") (name "unconnected-(U2A-PD14-Pad61)") (class "Default")
      (node (ref "U2") (pin "61") (pinfunction "PD14_61") (pintype "bidirectional+no_connect"))
    )
    (net (code "109") (name "unconnected-(U2A-PD15-Pad62)") (class "Default")
      (node (ref "U2") (pin "62") (pinfunction "PD15_62") (pintype "bidirectional+no_connect"))
    )
    (net (code "110") (name "unconnected-(U2A-PE0-Pad97)") (class "Default")
      (node (ref "U2") (pin "97") (pinfunction "PE0_97") (pintype "bidirectional+no_connect"))
    )
    (net (code "111") (name "unconnected-(U2A-PE1-Pad98)") (class "Default")
      (node (ref "U2") (pin "98") (pinfunction "PE1_98") (pintype "bidirectional+no_connect"))
    )
    (net (code "112") (name "unconnected-(U2A-PE2-Pad1)") (class "Default")
      (node (ref "U2") (pin "1") (pinfunction "PE2_1") (pintype "bidirectional+no_connect"))
    )
    (net (code "113") (name "unconnected-(U2A-PE3-Pad2)") (class "Default")
      (node (ref "U2") (pin "2") (pinfunction "PE3_2") (pintype "bidirectional+no_connect"))
    )
    (net (code "114") (name "unconnected-(U2A-PE4-Pad3)") (class "Default")
      (node (ref "U2") (pin "3") (pinfunction "PE4_3") (pintype "bidirectional+no_connect"))
    )
    (net (code "115") (name "unconnected-(U2A-PE5-Pad4)") (class "Default")
      (node (ref "U2") (pin "4") (pinfunction "PE5_4") (pintype "bidirectional+no_connect"))
    )
    (net (code "116") (name "unconnected-(U2A-PE6-Pad5)") (class "Default")
      (node (ref "U2") (pin "5") (pinfunction "PE6_5") (pintype "bidirectional+no_connect"))
    )
    (net (code "117") (name "unconnected-(U2A-PE7-Pad38)") (class "Default")
      (node (ref "U2") (pin "38") (pinfunction "PE7_38") (pintype "bidirectional+no_connect"))
    )
    (net (code "118") (name "unconnected-(U2A-PE8-Pad39)") (class "Default")
      (node (ref "U2") (pin "39") (pinfunction "PE8_39") (pintype "bidirectional+no_connect"))
    )
    (net (code "119") (name "unconnected-(U2A-PE9-Pad40)") (class "Default")
      (node (ref "U2") (pin "40") (pinfunction "PE9_40") (pintype "bidirectional+no_connect"))
    )
    (net (code "120") (name "unconnected-(U2A-PE10-Pad41)") (class "Default")
      (node (ref "U2") (pin "41") (pinfunction "PE10_41") (pintype "bidirectional+no_connect"))
    )
    (net (code "121") (name "unconnected-(U2A-PE11-Pad42)") (class "Default")
      (node (ref "U2") (pin "42") (pinfunction "PE11_42") (pintype "bidirectional+no_connect"))
    )
    (net (code "122") (name "unconnected-(U2A-PE12-Pad43)") (class "Default")
      (node (ref "U2") (pin "43") (pinfunction "PE12_43") (pintype "bidirectional+no_connect"))
    )
    (net (code "123") (name "unconnected-(U2A-PE13-Pad44)") (class "Default")
      (node (ref "U2") (pin "44") (pinfunction "PE13_44") (pintype "bidirectional+no_connect"))
    )
    (net (code "124") (name "unconnected-(U2A-PE14-Pad45)") (class "Default")
      (node (ref "U2") (pin "45") (pinfunction "PE14_45") (pintype "bidirectional+no_connect"))
    )
    (net (code "125") (name "unconnected-(U2A-PE15-Pad46)") (class "Default")
      (node (ref "U2") (pin "46") (pinfunction "PE15_46") (pintype "bidirectional+no_connect"))
    )
    (net (code "126") (name "unconnected-(U2B-NC-Pad73)") (class "Default")
      (node (ref "U2") (pin "73") (pinfunction "NC_73") (pintype "passive+no_connect"))
    )
    (net (code "127") (name "unconnected-(U3-n.c.-Pad5)") (class "Default")
      (node (ref "U3") (pin "5") (pinfunction "n.c._5") (pintype "passive+no_connect"))
    )
    (net (code "128") (name "unconnected-(USB_SLAVE-NC-Pad4)") (class "Default")
      (node (ref "USB_SLAVE") (pin "4") (pinfunction "NC_4") (pintype "passive+no_connect"))
    )
  )
)
